# Control_Levitador.net
KiCad netlist of a schematic drawn in Altium Designer
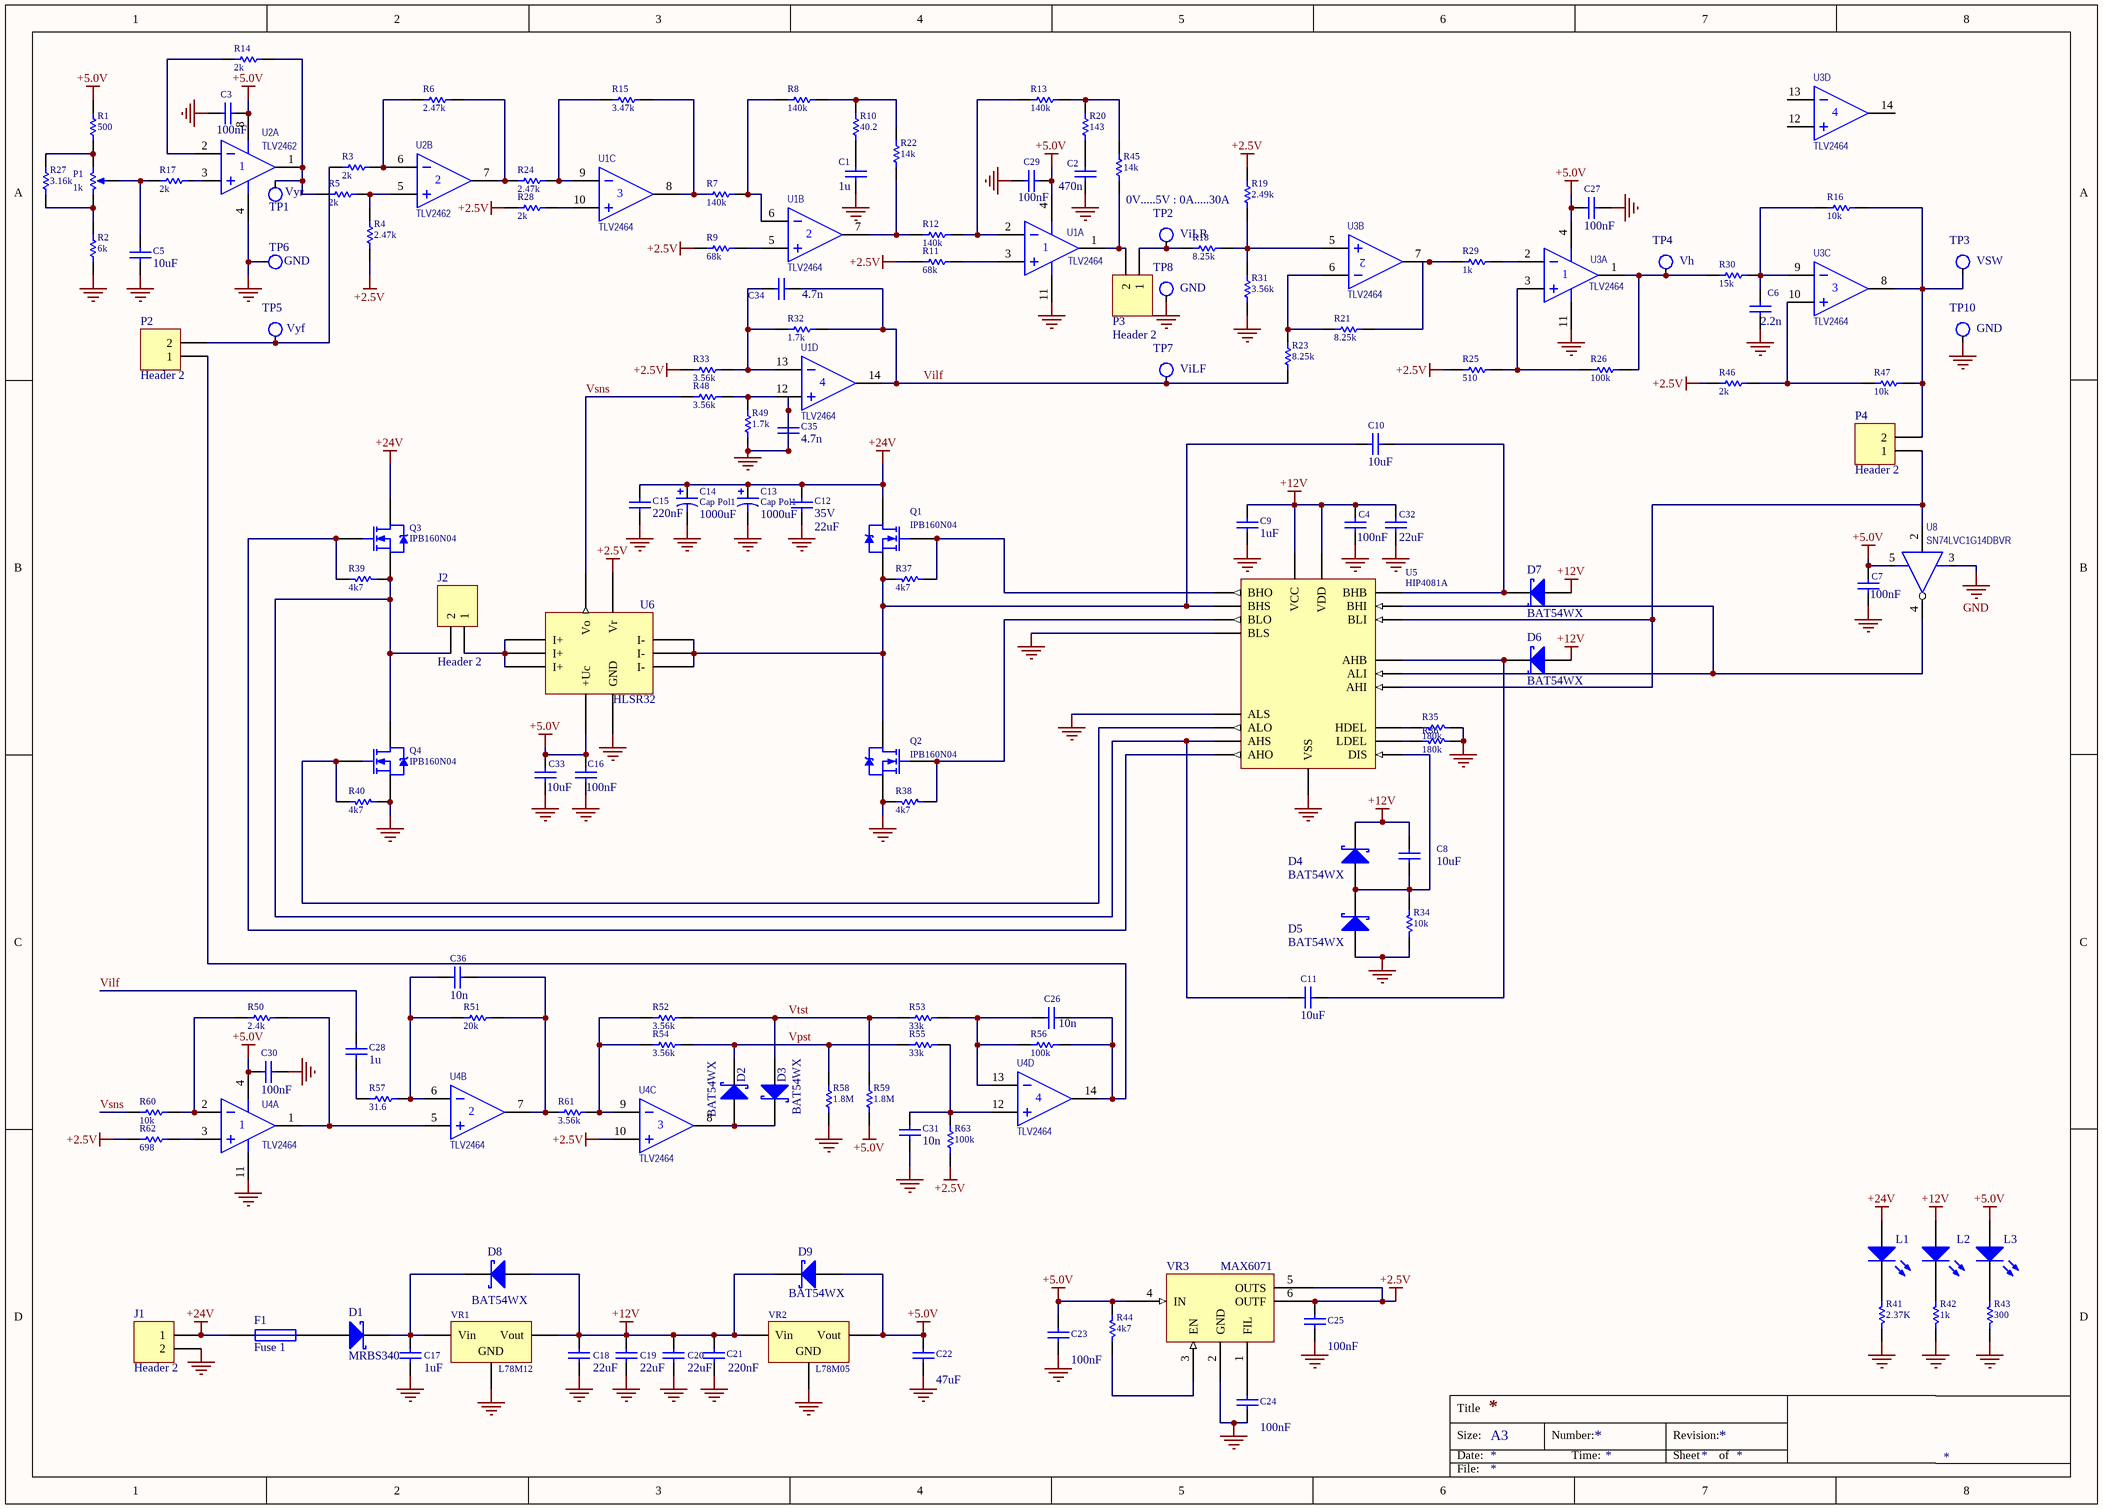
[diagram p0: Control Levitador.SchDoc]

(export (version "E")
  (design (tool "Eeschema 10.0.6"))
  (components
    (comp (ref "C1")
      (value "1u")
      (footprint "C1206")
      (description "Capacitor Chip 1206")
      (fields (field (name "VOLTAGE") "50V") (field (name "PUBLISHER") "Altium Limited"))
      (libsource (lib "Discretos") (part "C1206"))
    )
    (comp (ref "C2")
      (value "470n")
      (footprint "C1206")
      (description "Capacitor Chip 1206")
      (fields (field (name "VOLTAGE") "50V") (field (name "PUBLISHER") "Altium Limited"))
      (libsource (lib "Discretos") (part "C1206"))
    )
    (comp (ref "C3")
      (value "100nF")
      (footprint "C1206")
      (description "Capacitor Chip 1206")
      (fields (field (name "VOLTAGE") "50V") (field (name "PUBLISHER") "Altium Limited"))
      (libsource (lib "Discretos") (part "C1206"))
    )
    (comp (ref "C4")
      (value "100nF")
      (footprint "C1206")
      (description "Capacitor Chip 1206")
      (fields (field (name "VOLTAGE") "50V") (field (name "PUBLISHER") "Altium Limited"))
      (libsource (lib "Discretos") (part "C1206"))
    )
    (comp (ref "C5")
      (value "10uF")
      (footprint "C1206")
      (description "Capacitor Chip 1206")
      (fields (field (name "VOLTAGE") "50V") (field (name "PUBLISHER") "Altium Limited"))
      (libsource (lib "Discretos") (part "C1206"))
    )
    (comp (ref "C6")
      (value "2.2n")
      (footprint "C1206")
      (description "Capacitor Chip 1206")
      (fields (field (name "VOLTAGE") "50V") (field (name "PUBLISHER") "Altium Limited"))
      (libsource (lib "Discretos") (part "C1206"))
    )
    (comp (ref "C7")
      (value "100nF")
      (footprint "C1206")
      (description "Capacitor Chip 1206")
      (fields (field (name "VOLTAGE") "50V") (field (name "PUBLISHER") "Altium Limited"))
      (libsource (lib "Discretos") (part "C1206"))
    )
    (comp (ref "C8")
      (value "10uF")
      (footprint "C1206")
      (description "Capacitor Chip 1206")
      (fields (field (name "VOLTAGE") "50V") (field (name "PUBLISHER") "Altium Limited"))
      (libsource (lib "Discretos") (part "C1206"))
    )
    (comp (ref "C9")
      (value "1uF")
      (footprint "C1206")
      (description "Capacitor Chip 1206")
      (fields (field (name "VOLTAGE") "50V") (field (name "PUBLISHER") "Altium Limited"))
      (libsource (lib "Discretos") (part "C1206"))
    )
    (comp (ref "C10")
      (value "10uF")
      (footprint "C1206")
      (description "Capacitor Chip 1206")
      (fields (field (name "VOLTAGE") "50V") (field (name "PUBLISHER") "Altium Limited"))
      (libsource (lib "Discretos") (part "C1206"))
    )
    (comp (ref "C11")
      (value "10uF")
      (footprint "C1206")
      (description "Capacitor Chip 1206")
      (fields (field (name "VOLTAGE") "50V") (field (name "PUBLISHER") "Altium Limited"))
      (libsource (lib "Discretos") (part "C1206"))
    )
    (comp (ref "C12")
      (value "22uF")
      (footprint "C0805")
      (description "Capacitor Chip 1206")
      (fields (field (name "VOLTAGE") "35V") (field (name "PUBLISHER") "Altium Limited"))
      (libsource (lib "Discretos") (part "C1206"))
    )
    (comp (ref "C13")
      (value "Cap Pol1")
      (footprint "ALU CASE P")
      (description "Polarized Capacitor (Radial)")
      (fields (field (name "ALTIUM_VALUE") "1000uF") (field (name "PUBLISHER") "Altium Limited"))
      (libsource (lib "Miscellaneous Devices") (part "Cap Pol1"))
    )
    (comp (ref "C14")
      (value "Cap Pol1")
      (footprint "ALU CASE P")
      (description "Polarized Capacitor (Radial)")
      (fields (field (name "ALTIUM_VALUE") "1000uF") (field (name "PUBLISHER") "Altium Limited"))
      (libsource (lib "Miscellaneous Devices") (part "Cap Pol1"))
    )
    (comp (ref "C15")
      (value "220nF")
      (footprint "C1206")
      (description "Capacitor Chip 1206")
      (fields (field (name "VOLTAGE") "50V") (field (name "PUBLISHER") "Altium Limited"))
      (libsource (lib "Discretos") (part "C1206"))
    )
    (comp (ref "C16")
      (value "100nF")
      (footprint "C1206")
      (description "Capacitor Chip 1206")
      (fields (field (name "VOLTAGE") "50V") (field (name "PUBLISHER") "Altium Limited"))
      (libsource (lib "Discretos") (part "C1206"))
    )
    (comp (ref "C17")
      (value "1uF")
      (footprint "C1206")
      (description "Capacitor Chip 1206")
      (fields (field (name "VOLTAGE") "35V") (field (name "PUBLISHER") "Altium Limited"))
      (libsource (lib "Discretos") (part "C1206"))
    )
    (comp (ref "C18")
      (value "22uF")
      (footprint "C1206")
      (description "Capacitor Chip 1206")
      (fields (field (name "VOLTAGE") "16V") (field (name "PUBLISHER") "Altium Limited"))
      (libsource (lib "Discretos") (part "C1206"))
    )
    (comp (ref "C19")
      (value "22uF")
      (footprint "C1206")
      (description "Capacitor Chip 1206")
      (fields (field (name "VOLTAGE") "16V") (field (name "PUBLISHER") "Altium Limited"))
      (libsource (lib "Discretos") (part "C1206"))
    )
    (comp (ref "C20")
      (value "22uF")
      (footprint "C1206")
      (description "Capacitor Chip 1206")
      (fields (field (name "VOLTAGE") "16V") (field (name "PUBLISHER") "Altium Limited"))
      (libsource (lib "Discretos") (part "C1206"))
    )
    (comp (ref "C21")
      (value "220nF")
      (footprint "C1206")
      (description "Capacitor Chip 1206")
      (fields (field (name "VOLTAGE") "35V") (field (name "PUBLISHER") "Altium Limited"))
      (libsource (lib "Discretos") (part "C1206"))
    )
    (comp (ref "C22")
      (value "47uF")
      (footprint "C1206")
      (description "Capacitor Chip 1206")
      (fields (field (name "VOLTAGE") "6.3V") (field (name "PUBLISHER") "Altium Limited"))
      (libsource (lib "Discretos") (part "C1206"))
    )
    (comp (ref "C23")
      (value "100nF")
      (footprint "C1206")
      (description "Capacitor Chip 1206")
      (fields (field (name "VOLTAGE") "50V") (field (name "PUBLISHER") "Altium Limited"))
      (libsource (lib "Discretos") (part "C1206"))
    )
    (comp (ref "C24")
      (value "100nF")
      (footprint "C1206")
      (description "Capacitor Chip 1206")
      (fields (field (name "VOLTAGE") "50V") (field (name "PUBLISHER") "Altium Limited"))
      (libsource (lib "Discretos") (part "C1206"))
    )
    (comp (ref "C25")
      (value "100nF")
      (footprint "C1206")
      (description "Capacitor Chip 1206")
      (fields (field (name "VOLTAGE") "50V") (field (name "PUBLISHER") "Altium Limited"))
      (libsource (lib "Discretos") (part "C1206"))
    )
    (comp (ref "C26")
      (value "10n")
      (footprint "C1206")
      (description "Capacitor Chip 1206")
      (fields (field (name "VOLTAGE") "50V") (field (name "PUBLISHER") "Altium Limited"))
      (libsource (lib "Discretos") (part "C1206"))
    )
    (comp (ref "C27")
      (value "100nF")
      (footprint "C1206")
      (description "Capacitor Chip 1206")
      (fields (field (name "VOLTAGE") "50V") (field (name "PUBLISHER") "Altium Limited"))
      (libsource (lib "Discretos") (part "C1206"))
    )
    (comp (ref "C28")
      (value "1u")
      (footprint "C1206")
      (description "Capacitor Chip 1206")
      (fields (field (name "VOLTAGE") "50V") (field (name "PUBLISHER") "Altium Limited"))
      (libsource (lib "Discretos") (part "C1206"))
    )
    (comp (ref "C29")
      (value "100nF")
      (footprint "C1206")
      (description "Capacitor Chip 1206")
      (fields (field (name "VOLTAGE") "50V") (field (name "PUBLISHER") "Altium Limited"))
      (libsource (lib "Discretos") (part "C1206"))
    )
    (comp (ref "C30")
      (value "100nF")
      (footprint "C1206")
      (description "Capacitor Chip 1206")
      (fields (field (name "VOLTAGE") "50V") (field (name "PUBLISHER") "Altium Limited"))
      (libsource (lib "Discretos") (part "C1206"))
    )
    (comp (ref "C31")
      (value "10n")
      (footprint "C1206")
      (description "Capacitor Chip 1206")
      (fields (field (name "VOLTAGE") "50V") (field (name "PUBLISHER") "Altium Limited"))
      (libsource (lib "Discretos") (part "C1206"))
    )
    (comp (ref "C32")
      (value "22uF")
      (footprint "C1206")
      (description "Capacitor Chip 1206")
      (fields (field (name "VOLTAGE") "50V") (field (name "PUBLISHER") "Altium Limited"))
      (libsource (lib "Discretos") (part "C1206"))
    )
    (comp (ref "C33")
      (value "10uF")
      (footprint "C1206")
      (description "Capacitor Chip 1206")
      (fields (field (name "VOLTAGE") "50V") (field (name "PUBLISHER") "Altium Limited"))
      (libsource (lib "Discretos") (part "C1206"))
    )
    (comp (ref "C34")
      (value "4.7n")
      (footprint "C1206")
      (description "Capacitor Chip 1206")
      (fields (field (name "VOLTAGE") "50V") (field (name "PUBLISHER") "Altium Limited"))
      (libsource (lib "Discretos") (part "C1206"))
    )
    (comp (ref "C35")
      (value "4.7n")
      (footprint "C1206")
      (description "Capacitor Chip 1206")
      (fields (field (name "VOLTAGE") "50V") (field (name "PUBLISHER") "Altium Limited"))
      (libsource (lib "Discretos") (part "C1206"))
    )
    (comp (ref "C36")
      (value "10n")
      (footprint "C1206")
      (description "Capacitor Chip 1206")
      (fields (field (name "VOLTAGE") "50V") (field (name "PUBLISHER") "Altium Limited"))
      (libsource (lib "Discretos") (part "C1206"))
    )
    (comp (ref "D1")
      (value "MRBS340")
      (footprint "DO214AB")
      (description "Schottky Rectifier")
      (fields (field (name "PUBLISHER") "Altium Limited"))
      (libsource (lib "Levitador magnetico") (part "Diode 10TQ035"))
    )
    (comp (ref "D2")
      (value "BAT54WX")
      (footprint "SOD523")
      (description "Schottky Rectifier")
      (fields (field (name "PUBLISHER") "Altium Limited"))
      (libsource (lib "Levitador magnetico") (part "Diode 10TQ035"))
    )
    (comp (ref "D3")
      (value "BAT54WX")
      (footprint "SOD523")
      (description "Schottky Rectifier")
      (fields (field (name "PUBLISHER") "Altium Limited"))
      (libsource (lib "Levitador magnetico") (part "Diode 10TQ035"))
    )
    (comp (ref "D4")
      (value "BAT54WX")
      (footprint "SOD523")
      (description "Schottky Rectifier")
      (fields (field (name "PUBLISHER") "Altium Limited"))
      (libsource (lib "Levitador magnetico") (part "Diode 10TQ035"))
    )
    (comp (ref "D5")
      (value "BAT54WX")
      (footprint "SOD523")
      (description "Schottky Rectifier")
      (fields (field (name "PUBLISHER") "Altium Limited"))
      (libsource (lib "Levitador magnetico") (part "Diode 10TQ035"))
    )
    (comp (ref "D6")
      (value "BAT54WX")
      (footprint "SOD523")
      (description "Schottky Rectifier")
      (fields (field (name "PUBLISHER") "Altium Limited"))
      (libsource (lib "Levitador magnetico") (part "Diode 10TQ035"))
    )
    (comp (ref "D7")
      (value "BAT54WX")
      (footprint "SOD523")
      (description "Schottky Rectifier")
      (fields (field (name "PUBLISHER") "Altium Limited"))
      (libsource (lib "Levitador magnetico") (part "Diode 10TQ035"))
    )
    (comp (ref "D8")
      (value "BAT54WX")
      (footprint "SOD523")
      (description "Schottky Rectifier")
      (fields (field (name "PUBLISHER") "Altium Limited"))
      (libsource (lib "Levitador magnetico") (part "Diode 10TQ035"))
    )
    (comp (ref "D9")
      (value "BAT54WX")
      (footprint "SOD523")
      (description "Schottky Rectifier")
      (fields (field (name "PUBLISHER") "Altium Limited"))
      (libsource (lib "Levitador magnetico") (part "Diode 10TQ035"))
    )
    (comp (ref "F1")
      (value "Fuse 1")
      (footprint "R1206")
      (description "Fuse")
      (fields (field (name "PUBLISHER") "Altium Limited"))
      (libsource (lib "Miscellaneous Devices") (part "Fuse 1"))
    )
    (comp (ref "J1")
      (value "Header 2")
      (footprint "SMKDS5-2-9.5")
      (description "Header, 2-Pin")
      (fields (field (name "PUBLISHER") "Altium Limited"))
      (libsource (lib "") (part "Header 2_1"))
    )
    (comp (ref "J2")
      (value "Header 2")
      (footprint "SMKDS5-2-9.5")
      (description "Header, 2-Pin")
      (fields (field (name "PUBLISHER") "Altium Limited"))
      (libsource (lib "") (part "Header 2_2"))
    )
    (comp (ref "L1")
      (value "LED1")
      (footprint "LED 1206 RED")
      (description "Typical RED GaAs LED")
      (fields (field (name "PUBLISHER") "Altium Limited"))
      (libsource (lib "Miscellaneous Devices") (part "LED1"))
    )
    (comp (ref "L2")
      (value "LED1")
      (footprint "LED 1206 RED")
      (description "Typical RED GaAs LED")
      (fields (field (name "PUBLISHER") "Altium Limited"))
      (libsource (lib "Miscellaneous Devices") (part "LED1"))
    )
    (comp (ref "L3")
      (value "LED1")
      (footprint "LED 1206 RED")
      (description "Typical RED GaAs LED")
      (fields (field (name "PUBLISHER") "Altium Limited"))
      (libsource (lib "Miscellaneous Devices") (part "LED1"))
    )
    (comp (ref "P1")
      (value "1k")
      (footprint "BOR3")
      (description "Potentiometer")
      (fields (field (name "Comment") "RPot") (field (name "PUBLISHER") "Altium Limited"))
      (libsource (lib "Levitador magnetico") (part "RPot"))
    )
    (comp (ref "P2")
      (value "Header 2")
      (footprint "HDR1X2")
      (description "Header, 2-Pin")
      (fields (field (name "PUBLISHER") "Altium Limited"))
      (libsource (lib "Miscellaneous Connectors") (part "Header 2"))
    )
    (comp (ref "P3")
      (value "Header 2")
      (footprint "HDR1X2")
      (description "Header, 2-Pin")
      (fields (field (name "PUBLISHER") "Altium Limited"))
      (libsource (lib "") (part "Header 2_1"))
    )
    (comp (ref "P4")
      (value "Header 2")
      (footprint "HDR1X2")
      (description "Header, 2-Pin")
      (fields (field (name "PUBLISHER") "Altium Limited"))
      (libsource (lib "Miscellaneous Connectors") (part "Header 2"))
    )
    (comp (ref "Q1")
      (value "IPB160N04")
      (footprint "TO263-7S")
      (description "HEXFET N-Channel Power MOSFET")
      (fields (field (name "PUBLISHER") "Altium Limited"))
      (libsource (lib "Levitador magnetico") (part "IRF630S"))
    )
    (comp (ref "Q2")
      (value "IPB160N04")
      (footprint "TO263-7S")
      (description "HEXFET N-Channel Power MOSFET")
      (fields (field (name "PUBLISHER") "Altium Limited"))
      (libsource (lib "Levitador magnetico") (part "IRF630S"))
    )
    (comp (ref "Q3")
      (value "IPB160N04")
      (footprint "TO263-7S")
      (description "HEXFET N-Channel Power MOSFET")
      (fields (field (name "PUBLISHER") "Altium Limited"))
      (libsource (lib "Levitador magnetico") (part "IRF630S"))
    )
    (comp (ref "Q4")
      (value "IPB160N04")
      (footprint "TO263-7S")
      (description "HEXFET N-Channel Power MOSFET")
      (fields (field (name "PUBLISHER") "Altium Limited"))
      (libsource (lib "Levitador magnetico") (part "IRF630S"))
    )
    (comp (ref "R1")
      (value "500")
      (footprint "Levitador_GMI:R1206")
      (description "Resistor Chip; 1/8W;")
      (fields (field (name "MANUFACTURER") "Panasonic") (field (name "TOLERANCE") "1%"))
      (libsource (lib "Levitador_GMI") (part "R1206"))
    )
    (comp (ref "R2")
      (value "6k")
      (footprint "Levitador_GMI:R1206")
      (description "Resistor Chip; 1/8W;")
      (fields (field (name "MANUFACTURER") "Panasonic") (field (name "TOLERANCE") "1%"))
      (libsource (lib "Levitador_GMI") (part "R1206"))
    )
    (comp (ref "R3")
      (value "2k")
      (footprint "Levitador_GMI:R1206")
      (description "Resistor Chip; 1/8W;")
      (fields (field (name "MANUFACTURER") "Panasonic") (field (name "TOLERANCE") "1%"))
      (libsource (lib "Levitador_GMI") (part "R1206"))
    )
    (comp (ref "R4")
      (value "2.47k")
      (footprint "Levitador_GMI:R1206")
      (description "Resistor Chip; 1/8W;")
      (fields (field (name "MANUFACTURER") "Panasonic") (field (name "TOLERANCE") "1%"))
      (libsource (lib "Levitador_GMI") (part "R1206"))
    )
    (comp (ref "R5")
      (value "2k")
      (footprint "Levitador_GMI:R1206")
      (description "Resistor Chip; 1/8W;")
      (fields (field (name "MANUFACTURER") "Panasonic") (field (name "TOLERANCE") "1%"))
      (libsource (lib "Levitador_GMI") (part "R1206"))
    )
    (comp (ref "R6")
      (value "2.47k")
      (footprint "Levitador_GMI:R1206")
      (description "Resistor Chip; 1/8W;")
      (fields (field (name "MANUFACTURER") "Panasonic") (field (name "TOLERANCE") "1%"))
      (libsource (lib "Levitador_GMI") (part "R1206"))
    )
    (comp (ref "R7")
      (value "140k")
      (footprint "Levitador_GMI:R1206")
      (description "Resistor Chip; 1/8W;")
      (fields (field (name "MANUFACTURER") "Panasonic") (field (name "TOLERANCE") "1%"))
      (libsource (lib "Levitador_GMI") (part "R1206"))
    )
    (comp (ref "R8")
      (value "140k")
      (footprint "Levitador_GMI:R1206")
      (description "Resistor Chip; 1/8W;")
      (fields (field (name "MANUFACTURER") "Panasonic") (field (name "TOLERANCE") "1%"))
      (libsource (lib "Levitador_GMI") (part "R1206"))
    )
    (comp (ref "R9")
      (value "68k")
      (footprint "Levitador_GMI:R1206")
      (description "Resistor Chip; 1/8W;")
      (fields (field (name "MANUFACTURER") "Panasonic") (field (name "TOLERANCE") "1%"))
      (libsource (lib "Levitador_GMI") (part "R1206"))
    )
    (comp (ref "R10")
      (value "40.2")
      (footprint "Levitador_GMI:R1206")
      (description "Resistor Chip; 1/8W;")
      (fields (field (name "MANUFACTURER") "Panasonic") (field (name "TOLERANCE") "1%"))
      (libsource (lib "Levitador_GMI") (part "R1206"))
    )
    (comp (ref "R11")
      (value "68k")
      (footprint "Levitador_GMI:R1206")
      (description "Resistor Chip; 1/8W;")
      (fields (field (name "MANUFACTURER") "Panasonic") (field (name "TOLERANCE") "1%"))
      (libsource (lib "Levitador_GMI") (part "R1206"))
    )
    (comp (ref "R12")
      (value "140k")
      (footprint "Levitador_GMI:R1206")
      (description "Resistor Chip; 1/8W;")
      (fields (field (name "MANUFACTURER") "Panasonic") (field (name "TOLERANCE") "1%"))
      (libsource (lib "Levitador_GMI") (part "R1206"))
    )
    (comp (ref "R13")
      (value "140k")
      (footprint "Levitador_GMI:R1206")
      (description "Resistor Chip; 1/8W;")
      (fields (field (name "MANUFACTURER") "Panasonic") (field (name "TOLERANCE") "1%"))
      (libsource (lib "Levitador_GMI") (part "R1206"))
    )
    (comp (ref "R14")
      (value "2k")
      (footprint "Levitador_GMI:R1206")
      (description "Resistor Chip; 1/8W;")
      (fields (field (name "MANUFACTURER") "Panasonic") (field (name "TOLERANCE") "1%"))
      (libsource (lib "Levitador_GMI") (part "R1206"))
    )
    (comp (ref "R15")
      (value "3.47k")
      (footprint "Levitador_GMI:R1206")
      (description "Resistor Chip; 1/8W;")
      (fields (field (name "MANUFACTURER") "Panasonic") (field (name "TOLERANCE") "1%"))
      (libsource (lib "Levitador_GMI") (part "R1206"))
    )
    (comp (ref "R16")
      (value "10k")
      (footprint "Levitador_GMI:R1206")
      (description "Resistor Chip; 1/8W;")
      (fields (field (name "MANUFACTURER") "Panasonic") (field (name "TOLERANCE") "1%"))
      (libsource (lib "Levitador_GMI") (part "R1206"))
    )
    (comp (ref "R17")
      (value "2k")
      (footprint "Levitador_GMI:R1206")
      (description "Resistor Chip; 1/8W;")
      (fields (field (name "MANUFACTURER") "Panasonic") (field (name "TOLERANCE") "1%"))
      (libsource (lib "Levitador_GMI") (part "R1206"))
    )
    (comp (ref "R18")
      (value "8.25k")
      (footprint "Levitador_GMI:R1206")
      (description "Resistor Chip; 1/8W;")
      (fields (field (name "MANUFACTURER") "Panasonic") (field (name "TOLERANCE") "1%"))
      (libsource (lib "Levitador_GMI") (part "R1206"))
    )
    (comp (ref "R19")
      (value "2.49k")
      (footprint "Levitador_GMI:R1206")
      (description "Resistor Chip; 1/8W;")
      (fields (field (name "MANUFACTURER") "Panasonic") (field (name "TOLERANCE") "1%"))
      (libsource (lib "Levitador_GMI") (part "R1206"))
    )
    (comp (ref "R20")
      (value "143")
      (footprint "Levitador_GMI:R1206")
      (description "Resistor Chip; 1/8W;")
      (fields (field (name "MANUFACTURER") "Panasonic") (field (name "TOLERANCE") "1%"))
      (libsource (lib "Levitador_GMI") (part "R1206"))
    )
    (comp (ref "R21")
      (value "8.25k")
      (footprint "Levitador_GMI:R1206")
      (description "Resistor Chip; 1/8W;")
      (fields (field (name "MANUFACTURER") "Panasonic") (field (name "TOLERANCE") "1%"))
      (libsource (lib "Levitador_GMI") (part "R1206"))
    )
    (comp (ref "R22")
      (value "14k")
      (footprint "Levitador_GMI:R1206")
      (description "Resistor Chip; 1/8W;")
      (fields (field (name "MANUFACTURER") "Panasonic") (field (name "TOLERANCE") "1%"))
      (libsource (lib "Levitador_GMI") (part "R1206"))
    )
    (comp (ref "R23")
      (value "8.25k")
      (footprint "Levitador_GMI:R1206")
      (description "Resistor Chip; 1/8W;")
      (fields (field (name "MANUFACTURER") "Panasonic") (field (name "TOLERANCE") "1%"))
      (libsource (lib "Levitador_GMI") (part "R1206"))
    )
    (comp (ref "R24")
      (value "2.47k")
      (footprint "Levitador_GMI:R1206")
      (description "Resistor Chip; 1/8W;")
      (fields (field (name "MANUFACTURER") "Panasonic") (field (name "TOLERANCE") "1%"))
      (libsource (lib "Levitador_GMI") (part "R1206"))
    )
    (comp (ref "R25")
      (value "510")
      (footprint "Levitador_GMI:R1206")
      (description "Resistor Chip; 1/8W;")
      (fields (field (name "MANUFACTURER") "Panasonic") (field (name "TOLERANCE") "1%"))
      (libsource (lib "Levitador_GMI") (part "R1206"))
    )
    (comp (ref "R26")
      (value "100k")
      (footprint "Levitador_GMI:R1206")
      (description "Resistor Chip; 1/8W;")
      (fields (field (name "MANUFACTURER") "Panasonic") (field (name "TOLERANCE") "1%"))
      (libsource (lib "Levitador_GMI") (part "R1206"))
    )
    (comp (ref "R27")
      (value "3.16k")
      (footprint "Levitador_GMI:R1206")
      (description "Resistor Chip; 1/8W;")
      (fields (field (name "MANUFACTURER") "Panasonic") (field (name "TOLERANCE") "1%"))
      (libsource (lib "Levitador_GMI") (part "R1206"))
    )
    (comp (ref "R28")
      (value "2k")
      (footprint "Levitador_GMI:R1206")
      (description "Resistor Chip; 1/8W;")
      (fields (field (name "MANUFACTURER") "Panasonic") (field (name "TOLERANCE") "1%"))
      (libsource (lib "Levitador_GMI") (part "R1206"))
    )
    (comp (ref "R29")
      (value "1k")
      (footprint "Levitador_GMI:R1206")
      (description "Resistor Chip; 1/8W;")
      (fields (field (name "MANUFACTURER") "Panasonic") (field (name "TOLERANCE") "1%"))
      (libsource (lib "Levitador_GMI") (part "R1206"))
    )
    (comp (ref "R30")
      (value "15k")
      (footprint "Levitador_GMI:R1206")
      (description "Resistor Chip; 1/8W;")
      (fields (field (name "MANUFACTURER") "Panasonic") (field (name "TOLERANCE") "1%"))
      (libsource (lib "Levitador_GMI") (part "R1206"))
    )
    (comp (ref "R31")
      (value "3.56k")
      (footprint "Levitador_GMI:R1206")
      (description "Resistor Chip; 1/8W;")
      (fields (field (name "MANUFACTURER") "Panasonic") (field (name "TOLERANCE") "1%"))
      (libsource (lib "Levitador_GMI") (part "R1206"))
    )
    (comp (ref "R32")
      (value "1.7k")
      (footprint "Levitador_GMI:R1206")
      (description "Resistor Chip; 1/8W;")
      (fields (field (name "MANUFACTURER") "Panasonic") (field (name "TOLERANCE") "1%"))
      (libsource (lib "Levitador_GMI") (part "R1206"))
    )
    (comp (ref "R33")
      (value "3.56k")
      (footprint "Levitador_GMI:R1206")
      (description "Resistor Chip; 1/8W;")
      (fields (field (name "MANUFACTURER") "Panasonic") (field (name "TOLERANCE") "1%"))
      (libsource (lib "Levitador_GMI") (part "R1206"))
    )
    (comp (ref "R34")
      (value "10k")
      (footprint "Levitador_GMI:R1206")
      (description "Resistor Chip; 1/8W;")
      (fields (field (name "MANUFACTURER") "Panasonic") (field (name "TOLERANCE") "1%"))
      (libsource (lib "Levitador_GMI") (part "R1206"))
    )
    (comp (ref "R35")
      (value "180k")
      (footprint "Levitador_GMI:R1206")
      (description "Resistor Chip; 1/8W;")
      (fields (field (name "MANUFACTURER") "Panasonic") (field (name "TOLERANCE") "1%"))
      (libsource (lib "Levitador_GMI") (part "R1206"))
    )
    (comp (ref "R36")
      (value "180k")
      (footprint "Levitador_GMI:R1206")
      (description "Resistor Chip; 1/8W;")
      (fields (field (name "MANUFACTURER") "Panasonic") (field (name "TOLERANCE") "1%"))
      (libsource (lib "Levitador_GMI") (part "R1206"))
    )
    (comp (ref "R37")
      (value "4k7")
      (footprint "Levitador_GMI:R1206")
      (description "Resistor Chip; 1/8W;")
      (fields (field (name "MANUFACTURER") "Panasonic") (field (name "TOLERANCE") "1%"))
      (libsource (lib "Levitador_GMI") (part "R1206"))
    )
    (comp (ref "R38")
      (value "4k7")
      (footprint "Levitador_GMI:R1206")
      (description "Resistor Chip; 1/8W;")
      (fields (field (name "MANUFACTURER") "Panasonic") (field (name "TOLERANCE") "1%"))
      (libsource (lib "Levitador_GMI") (part "R1206"))
    )
    (comp (ref "R39")
      (value "4k7")
      (footprint "Levitador_GMI:R1206")
      (description "Resistor Chip; 1/8W;")
      (fields (field (name "MANUFACTURER") "Panasonic") (field (name "TOLERANCE") "1%"))
      (libsource (lib "Levitador_GMI") (part "R1206"))
    )
    (comp (ref "R40")
      (value "4k7")
      (footprint "Levitador_GMI:R1206")
      (description "Resistor Chip; 1/8W;")
      (fields (field (name "MANUFACTURER") "Panasonic") (field (name "TOLERANCE") "1%"))
      (libsource (lib "Levitador_GMI") (part "R1206"))
    )
    (comp (ref "R41")
      (value "2.37K")
      (footprint "Levitador_GMI:R1206")
      (description "Resistor Chip; 1/8W;")
      (fields (field (name "MANUFACTURER") "Panasonic") (field (name "TOLERANCE") "1%"))
      (libsource (lib "Levitador_GMI") (part "R1206"))
    )
    (comp (ref "R42")
      (value "1k")
      (footprint "Levitador_GMI:R1206")
      (description "Resistor Chip; 1/8W;")
      (fields (field (name "MANUFACTURER") "Panasonic") (field (name "TOLERANCE") "1%"))
      (libsource (lib "Levitador_GMI") (part "R1206"))
    )
    (comp (ref "R43")
      (value "300")
      (footprint "Levitador_GMI:R1206")
      (description "Resistor Chip; 1/8W;")
      (fields (field (name "MANUFACTURER") "Panasonic") (field (name "TOLERANCE") "1%"))
      (libsource (lib "Levitador_GMI") (part "R1206"))
    )
    (comp (ref "R44")
      (value "4k7")
      (footprint "Levitador_GMI:R1206")
      (description "Resistor Chip; 1/8W;")
      (fields (field (name "MANUFACTURER") "Panasonic") (field (name "TOLERANCE") "1%"))
      (libsource (lib "Levitador_GMI") (part "R1206"))
    )
    (comp (ref "R45")
      (value "14k")
      (footprint "Levitador_GMI:R1206")
      (description "Resistor Chip; 1/8W;")
      (fields (field (name "MANUFACTURER") "Panasonic") (field (name "TOLERANCE") "1%"))
      (libsource (lib "Levitador_GMI") (part "R1206"))
    )
    (comp (ref "R46")
      (value "2k")
      (footprint "Levitador_GMI:R1206")
      (description "Resistor Chip; 1/8W;")
      (fields (field (name "MANUFACTURER") "Panasonic") (field (name "TOLERANCE") "1%"))
      (libsource (lib "Levitador_GMI") (part "R1206"))
    )
    (comp (ref "R47")
      (value "10k")
      (footprint "Levitador_GMI:R1206")
      (description "Resistor Chip; 1/8W;")
      (fields (field (name "MANUFACTURER") "Panasonic") (field (name "TOLERANCE") "1%"))
      (libsource (lib "Levitador_GMI") (part "R1206"))
    )
    (comp (ref "R48")
      (value "3.56k")
      (footprint "Levitador_GMI:R1206")
      (description "Resistor Chip; 1/8W;")
      (fields (field (name "MANUFACTURER") "Panasonic") (field (name "TOLERANCE") "1%"))
      (libsource (lib "Levitador_GMI") (part "R1206"))
    )
    (comp (ref "R49")
      (value "1.7k")
      (footprint "Levitador_GMI:R1206")
      (description "Resistor Chip; 1/8W;")
      (fields (field (name "MANUFACTURER") "Panasonic") (field (name "TOLERANCE") "1%"))
      (libsource (lib "Levitador_GMI") (part "R1206"))
    )
    (comp (ref "R50")
      (value "2.4k")
      (footprint "Levitador_GMI:R1206")
      (description "Resistor Chip; 1/8W;")
      (fields (field (name "MANUFACTURER") "Panasonic") (field (name "TOLERANCE") "1%"))
      (libsource (lib "Levitador_GMI") (part "R1206"))
    )
    (comp (ref "R51")
      (value "20k")
      (footprint "Levitador_GMI:R1206")
      (description "Resistor Chip; 1/8W;")
      (fields (field (name "MANUFACTURER") "Panasonic") (field (name "TOLERANCE") "1%"))
      (libsource (lib "Levitador_GMI") (part "R1206"))
    )
    (comp (ref "R52")
      (value "3.56k")
      (footprint "Levitador_GMI:R1206")
      (description "Resistor Chip; 1/8W;")
      (fields (field (name "MANUFACTURER") "Panasonic") (field (name "TOLERANCE") "1%"))
      (libsource (lib "Levitador_GMI") (part "R1206"))
    )
    (comp (ref "R53")
      (value "33k")
      (footprint "Levitador_GMI:R1206")
      (description "Resistor Chip; 1/8W;")
      (fields (field (name "MANUFACTURER") "Panasonic") (field (name "TOLERANCE") "1%"))
      (libsource (lib "Levitador_GMI") (part "R1206"))
    )
    (comp (ref "R54")
      (value "3.56k")
      (footprint "Levitador_GMI:R1206")
      (description "Resistor Chip; 1/8W;")
      (fields (field (name "MANUFACTURER") "Panasonic") (field (name "TOLERANCE") "1%"))
      (libsource (lib "Levitador_GMI") (part "R1206"))
    )
    (comp (ref "R55")
      (value "33k")
      (footprint "Levitador_GMI:R1206")
      (description "Resistor Chip; 1/8W;")
      (fields (field (name "MANUFACTURER") "Panasonic") (field (name "TOLERANCE") "1%"))
      (libsource (lib "Levitador_GMI") (part "R1206"))
    )
    (comp (ref "R56")
      (value "100k")
      (footprint "Levitador_GMI:R1206")
      (description "Resistor Chip; 1/8W;")
      (fields (field (name "MANUFACTURER") "Panasonic") (field (name "TOLERANCE") "1%"))
      (libsource (lib "Levitador_GMI") (part "R1206"))
    )
    (comp (ref "R57")
      (value "31.6")
      (footprint "Levitador_GMI:R1206")
      (description "Resistor Chip; 1/8W;")
      (fields (field (name "MANUFACTURER") "Panasonic") (field (name "TOLERANCE") "1%"))
      (libsource (lib "Levitador_GMI") (part "R1206"))
    )
    (comp (ref "R58")
      (value "1.8M")
      (footprint "Levitador_GMI:R1206")
      (description "Resistor Chip; 1/8W;")
      (fields (field (name "MANUFACTURER") "Panasonic") (field (name "TOLERANCE") "1%"))
      (libsource (lib "Levitador_GMI") (part "R1206"))
    )
    (comp (ref "R59")
      (value "1.8M")
      (footprint "Levitador_GMI:R1206")
      (description "Resistor Chip; 1/8W;")
      (fields (field (name "MANUFACTURER") "Panasonic") (field (name "TOLERANCE") "1%"))
      (libsource (lib "Levitador_GMI") (part "R1206"))
    )
    (comp (ref "R60")
      (value "10k")
      (footprint "Levitador_GMI:R1206")
      (description "Resistor Chip; 1/8W;")
      (fields (field (name "MANUFACTURER") "Panasonic") (field (name "TOLERANCE") "1%"))
      (libsource (lib "Levitador_GMI") (part "R1206"))
    )
    (comp (ref "R61")
      (value "3.56k")
      (footprint "Levitador_GMI:R1206")
      (description "Resistor Chip; 1/8W;")
      (fields (field (name "MANUFACTURER") "Panasonic") (field (name "TOLERANCE") "1%"))
      (libsource (lib "Levitador_GMI") (part "R1206"))
    )
    (comp (ref "R62")
      (value "698")
      (footprint "Levitador_GMI:R1206")
      (description "Resistor Chip; 1/8W;")
      (fields (field (name "MANUFACTURER") "Panasonic") (field (name "TOLERANCE") "1%"))
      (libsource (lib "Levitador_GMI") (part "R1206"))
    )
    (comp (ref "R63")
      (value "100k")
      (footprint "Levitador_GMI:R1206")
      (description "Resistor Chip; 1/8W;")
      (fields (field (name "MANUFACTURER") "Panasonic") (field (name "TOLERANCE") "1%"))
      (libsource (lib "Levitador_GMI") (part "R1206"))
    )
    (comp (ref "TP1")
      (value "Vyr")
      (footprint "TestPoint Keystone 5000 Silver-Red")
      (description "Test point")
      (libsource (lib "Terminales") (part "Tespoint"))
    )
    (comp (ref "TP2")
      (value "ViLR")
      (footprint "TestPoint Keystone 5000 Silver-Red")
      (description "Test point")
      (libsource (lib "Terminales") (part "Tespoint"))
    )
    (comp (ref "TP3")
      (value "VSW")
      (footprint "TestPoint Keystone 5000 Silver-Red")
      (description "Test point")
      (libsource (lib "Terminales") (part "Tespoint"))
    )
    (comp (ref "TP4")
      (value "Vh")
      (footprint "TestPoint Keystone 5000 Silver-Red")
      (description "Test point")
      (libsource (lib "Terminales") (part "Tespoint"))
    )
    (comp (ref "TP5")
      (value "Vyf")
      (footprint "TestPoint Keystone 5000 Silver-Red")
      (description "Test point")
      (libsource (lib "Terminales") (part "Tespoint"))
    )
    (comp (ref "TP6")
      (value "GND")
      (footprint "TestPoint Keystone 5000 Silver-Red")
      (description "Test point")
      (libsource (lib "Terminales") (part "Tespoint"))
    )
    (comp (ref "TP7")
      (value "ViLF")
      (footprint "TestPoint Keystone 5000 Silver-Red")
      (description "Test point")
      (libsource (lib "Terminales") (part "Tespoint"))
    )
    (comp (ref "TP8")
      (value "GND")
      (footprint "TestPoint Keystone 5000 Silver-Red")
      (description "Test point")
      (libsource (lib "Terminales") (part "Tespoint"))
    )
    (comp (ref "TP10")
      (value "GND")
      (footprint "TestPoint Keystone 5000 Silver-Red")
      (description "Test point")
      (libsource (lib "Terminales") (part "Tespoint"))
    )
    (comp (ref "U1")
      (value "TLV2464")
      (footprint "SOIC14")
      (description "Dual Low-Power Operational Amplifier")
      (fields (field (name "PUBLISHER") "Altium Limited"))
      (libsource (lib "Levitador") (part "TLV2464"))
    )
    (comp (ref "U2")
      (value "TLV2462")
      (footprint "SOIC8")
      (description "Dual Low-Power Operational Amplifier")
      (fields (field (name "PUBLISHER") "Altium Limited"))
      (libsource (lib "CTRL_Levitador") (part "TLV2462"))
    )
    (comp (ref "U3")
      (value "TLV2464")
      (footprint "SOIC14")
      (description "Dual Low-Power Operational Amplifier")
      (fields (field (name "PUBLISHER") "Altium Limited"))
      (libsource (lib "Levitador") (part "TLV2464"))
    )
    (comp (ref "U4")
      (value "TLV2464")
      (footprint "SOIC14")
      (description "Dual Low-Power Operational Amplifier")
      (fields (field (name "PUBLISHER") "Altium Limited"))
      (libsource (lib "Levitador") (part "TLV2464"))
    )
    (comp (ref "U5")
      (value "HIP4081A")
      (footprint "SOIC20")
      (description "INTERSIL, 80V, 2.5A peak, High Frequency Full Bridge FET Driver")
      (fields (field (name "MANUFACTURER_PART_NUMBER") "HIP4081AIBZ"))
      (libsource (lib "Levitador_GMI") (part "HIP4081A"))
    )
    (comp (ref "U6")
      (value "HLSR32")
      (footprint "HSLR-P")
      (description "Hall Effect Current Sensor")
      (libsource (lib "Sensores") (part "HSLR32"))
    )
    (comp (ref "U8")
      (value "SN74LVC1G14DBVR")
      (footprint "SOT23-5")
      (description "Schmitt-Trigger Inverter")
      (fields (field (name "PUBLISHER") "Altium Limited"))
      (libsource (lib "Levitador") (part "SN74LVC1G14DBVR"))
    )
    (comp (ref "VR1")
      (value "L78M12")
      (footprint "TO252-AA")
      (description "Voltage Regulator")
      (fields (field (name "PUBLISHER") "Altium Limited"))
      (libsource (lib "Levitador magnetico") (part "Volt Reg"))
    )
    (comp (ref "VR2")
      (value "L78M05")
      (footprint "TO252-AA")
      (description "Voltage Regulator")
      (fields (field (name "PUBLISHER") "Altium Limited"))
      (libsource (lib "Levitador magnetico") (part "Volt Reg"))
    )
    (comp (ref "VR3")
      (value "MAX6071")
      (footprint "SOT23-6")
      (libsource (lib "Fuentes Alimentacion") (part "MAX6070"))
    )
  )
  (nets
    (net (code "1") (name "+2.5V") (class "Default")
      (node (ref "C25") (pin "2") (pinfunction "2_2") (pintype "passive"))
      (node (ref "R11") (pin "2") (pinfunction "2_2") (pintype "passive"))
      (node (ref "R19") (pin "2") (pinfunction "2_2") (pintype "passive"))
      (node (ref "R25") (pin "2") (pinfunction "2_2") (pintype "passive"))
      (node (ref "R28") (pin "1") (pinfunction "1_1") (pintype "passive"))
      (node (ref "R33") (pin "1") (pinfunction "1_1") (pintype "passive"))
      (node (ref "R4") (pin "1") (pinfunction "1_1") (pintype "passive"))
      (node (ref "R46") (pin "2") (pinfunction "2_2") (pintype "passive"))
      (node (ref "R62") (pin "1") (pinfunction "1_1") (pintype "passive"))
      (node (ref "R63") (pin "2") (pinfunction "2_2") (pintype "passive"))
      (node (ref "R9") (pin "1") (pinfunction "1_1") (pintype "passive"))
      (node (ref "U4") (pin "10") (pinfunction "IN+_10") (pintype "passive"))
      (node (ref "U6") (pin "1") (pinfunction "Vr_1") (pintype "passive"))
      (node (ref "VR3") (pin "5") (pinfunction "OUTS_5") (pintype "passive"))
      (node (ref "VR3") (pin "6") (pinfunction "OUTF_6") (pintype "passive"))
    )
    (net (code "2") (name "+5.0V") (class "Default")
      (node (ref "C16") (pin "2") (pinfunction "2_2") (pintype "passive"))
      (node (ref "C22") (pin "2") (pinfunction "2_2") (pintype "passive"))
      (node (ref "C23") (pin "2") (pinfunction "2_2") (pintype "passive"))
      (node (ref "C27") (pin "2") (pinfunction "2_2") (pintype "passive"))
      (node (ref "C29") (pin "2") (pinfunction "2_2") (pintype "passive"))
      (node (ref "C3") (pin "2") (pinfunction "2_2") (pintype "passive"))
      (node (ref "C30") (pin "2") (pinfunction "2_2") (pintype "passive"))
      (node (ref "C33") (pin "2") (pinfunction "2_2") (pintype "passive"))
      (node (ref "C7") (pin "2") (pinfunction "2_2") (pintype "passive"))
      (node (ref "D9") (pin "1") (pinfunction "A_1") (pintype "passive"))
      (node (ref "L3") (pin "1") (pinfunction "A_1") (pintype "passive"))
      (node (ref "R1") (pin "2") (pinfunction "2_2") (pintype "passive"))
      (node (ref "R44") (pin "2") (pinfunction "2_2") (pintype "passive"))
      (node (ref "R59") (pin "1") (pinfunction "1_1") (pintype "passive"))
      (node (ref "U1") (pin "4") (pinfunction "V+_4") (pintype "power_in"))
      (node (ref "U2") (pin "8") (pinfunction "V+_8") (pintype "power_in"))
      (node (ref "U3") (pin "4") (pinfunction "V+_4") (pintype "power_in"))
      (node (ref "U4") (pin "4") (pinfunction "V+_4") (pintype "power_in"))
      (node (ref "U6") (pin "4") (pinfunction "+Uc_4") (pintype "power_in"))
      (node (ref "U8") (pin "5") (pinfunction "V+_5") (pintype "power_in"))
      (node (ref "VR2") (pin "3") (pinfunction "Vout_3") (pintype "passive"))
      (node (ref "VR3") (pin "4") (pinfunction "IN_4") (pintype "input"))
    )
    (net (code "3") (name "+12V") (class "Default")
      (node (ref "C18") (pin "2") (pinfunction "2_2") (pintype "passive"))
      (node (ref "C19") (pin "2") (pinfunction "2_2") (pintype "passive"))
      (node (ref "C20") (pin "2") (pinfunction "2_2") (pintype "passive"))
      (node (ref "C21") (pin "2") (pinfunction "2_2") (pintype "passive"))
      (node (ref "C32") (pin "2") (pinfunction "2_2") (pintype "passive"))
      (node (ref "C4") (pin "2") (pinfunction "2_2") (pintype "passive"))
      (node (ref "C8") (pin "1") (pinfunction "1_1") (pintype "passive"))
      (node (ref "C9") (pin "2") (pinfunction "2_2") (pintype "passive"))
      (node (ref "D4") (pin "2") (pinfunction "K_2") (pintype "passive"))
      (node (ref "D6") (pin "1") (pinfunction "A_1") (pintype "passive"))
      (node (ref "D7") (pin "1") (pinfunction "A_1") (pintype "passive"))
      (node (ref "D8") (pin "1") (pinfunction "A_1") (pintype "passive"))
      (node (ref "D9") (pin "2") (pinfunction "K_2") (pintype "passive"))
      (node (ref "L2") (pin "1") (pinfunction "A_1") (pintype "passive"))
      (node (ref "U5") (pin "15") (pinfunction "VCC_15") (pintype "power_in"))
      (node (ref "U5") (pin "16") (pinfunction "VDD_16") (pintype "power_in"))
      (node (ref "VR1") (pin "3") (pinfunction "Vout_3") (pintype "passive"))
      (node (ref "VR2") (pin "1") (pinfunction "Vin_1") (pintype "passive"))
    )
    (net (code "4") (name "+24V") (class "Default")
      (node (ref "C12") (pin "2") (pinfunction "2_2") (pintype "passive"))
      (node (ref "C13") (pin "1") (pinfunction "1_1") (pintype "passive"))
      (node (ref "C14") (pin "1") (pinfunction "1_1") (pintype "passive"))
      (node (ref "C15") (pin "2") (pinfunction "2_2") (pintype "passive"))
      (node (ref "F1") (pin "1") (pinfunction "1_1") (pintype "passive"))
      (node (ref "J1") (pin "1") (pinfunction "1_1") (pintype "passive"))
      (node (ref "L1") (pin "1") (pinfunction "A_1") (pintype "passive"))
      (node (ref "Q1") (pin "4") (pinfunction "D_4") (pintype "passive"))
      (node (ref "Q3") (pin "4") (pinfunction "D_4") (pintype "passive"))
    )
    (net (code "5") (name "/Vilf") (class "Default")
      (node (ref "C28") (pin "1") (pinfunction "1_1") (pintype "passive"))
      (node (ref "C34") (pin "2") (pinfunction "2_2") (pintype "passive"))
      (node (ref "R23") (pin "1") (pinfunction "1_1") (pintype "passive"))
      (node (ref "R32") (pin "2") (pinfunction "2_2") (pintype "passive"))
      (node (ref "TP7") (pin "1") (pinfunction "1_1") (pintype "passive"))
      (node (ref "U1") (pin "14") (pinfunction "OUT_14") (pintype "passive"))
    )
    (net (code "6") (name "/Vpst") (class "Default")
      (node (ref "D2") (pin "2") (pinfunction "K_2") (pintype "passive"))
      (node (ref "R54") (pin "2") (pinfunction "2_2") (pintype "passive"))
      (node (ref "R55") (pin "2") (pinfunction "2_2") (pintype "passive"))
      (node (ref "R58") (pin "2") (pinfunction "2_2") (pintype "passive"))
    )
    (net (code "7") (name "/Vsns") (class "Default")
      (node (ref "R48") (pin "2") (pinfunction "2_2") (pintype "passive"))
      (node (ref "R60") (pin "1") (pinfunction "1_1") (pintype "passive"))
      (node (ref "U6") (pin "2") (pinfunction "Vo_2") (pintype "output"))
    )
    (net (code "8") (name "/Vtst") (class "Default")
      (node (ref "D3") (pin "1") (pinfunction "A_1") (pintype "passive"))
      (node (ref "R52") (pin "2") (pinfunction "2_2") (pintype "passive"))
      (node (ref "R53") (pin "2") (pinfunction "2_2") (pintype "passive"))
      (node (ref "R59") (pin "2") (pinfunction "2_2") (pintype "passive"))
    )
    (net (code "9") (name "GND") (class "Default")
      (node (ref "C1") (pin "1") (pinfunction "1_1") (pintype "passive"))
      (node (ref "C12") (pin "1") (pinfunction "1_1") (pintype "passive"))
      (node (ref "C13") (pin "2") (pinfunction "2_2") (pintype "passive"))
      (node (ref "C14") (pin "2") (pinfunction "2_2") (pintype "passive"))
      (node (ref "C15") (pin "1") (pinfunction "1_1") (pintype "passive"))
      (node (ref "C16") (pin "1") (pinfunction "1_1") (pintype "passive"))
      (node (ref "C17") (pin "1") (pinfunction "1_1") (pintype "passive"))
      (node (ref "C18") (pin "1") (pinfunction "1_1") (pintype "passive"))
      (node (ref "C19") (pin "1") (pinfunction "1_1") (pintype "passive"))
      (node (ref "C2") (pin "1") (pinfunction "1_1") (pintype "passive"))
      (node (ref "C20") (pin "1") (pinfunction "1_1") (pintype "passive"))
      (node (ref "C21") (pin "1") (pinfunction "1_1") (pintype "passive"))
      (node (ref "C22") (pin "1") (pinfunction "1_1") (pintype "passive"))
      (node (ref "C23") (pin "1") (pinfunction "1_1") (pintype "passive"))
      (node (ref "C24") (pin "1") (pinfunction "1_1") (pintype "passive"))
      (node (ref "C25") (pin "1") (pinfunction "1_1") (pintype "passive"))
      (node (ref "C27") (pin "1") (pinfunction "1_1") (pintype "passive"))
      (node (ref "C29") (pin "1") (pinfunction "1_1") (pintype "passive"))
      (node (ref "C3") (pin "1") (pinfunction "1_1") (pintype "passive"))
      (node (ref "C30") (pin "1") (pinfunction "1_1") (pintype "passive"))
      (node (ref "C31") (pin "1") (pinfunction "1_1") (pintype "passive"))
      (node (ref "C32") (pin "1") (pinfunction "1_1") (pintype "passive"))
      (node (ref "C33") (pin "1") (pinfunction "1_1") (pintype "passive"))
      (node (ref "C35") (pin "1") (pinfunction "1_1") (pintype "passive"))
      (node (ref "C35") (pin "2") (pinfunction "2_2") (pintype "passive"))
      (node (ref "C4") (pin "1") (pinfunction "1_1") (pintype "passive"))
      (node (ref "C5") (pin "1") (pinfunction "1_1") (pintype "passive"))
      (node (ref "C6") (pin "1") (pinfunction "1_1") (pintype "passive"))
      (node (ref "C7") (pin "1") (pinfunction "1_1") (pintype "passive"))
      (node (ref "C9") (pin "1") (pinfunction "1_1") (pintype "passive"))
      (node (ref "D5") (pin "1") (pinfunction "A_1") (pintype "passive"))
      (node (ref "J1") (pin "2") (pinfunction "2_2") (pintype "passive"))
      (node (ref "Q2") (pin "2") (pinfunction "S_2") (pintype "passive"))
      (node (ref "Q2") (pin "3") (pinfunction "S_3") (pintype "passive"))
      (node (ref "Q2") (pin "5") (pinfunction "S_5") (pintype "passive"))
      (node (ref "Q2") (pin "6") (pinfunction "S_6") (pintype "passive"))
      (node (ref "Q2") (pin "7") (pinfunction "S_7") (pintype "passive"))
      (node (ref "Q4") (pin "2") (pinfunction "S_2") (pintype "passive"))
      (node (ref "Q4") (pin "3") (pinfunction "S_3") (pintype "passive"))
      (node (ref "Q4") (pin "5") (pinfunction "S_5") (pintype "passive"))
      (node (ref "Q4") (pin "6") (pinfunction "S_6") (pintype "passive"))
      (node (ref "Q4") (pin "7") (pinfunction "S_7") (pintype "passive"))
      (node (ref "R2") (pin "1") (pinfunction "1_1") (pintype "passive"))
      (node (ref "R31") (pin "1") (pinfunction "1_1") (pintype "passive"))
      (node (ref "R34") (pin "2") (pinfunction "2_2") (pintype "passive"))
      (node (ref "R35") (pin "1") (pinfunction "1_1") (pintype "passive"))
      (node (ref "R36") (pin "1") (pinfunction "1_1") (pintype "passive"))
      (node (ref "R38") (pin "2") (pinfunction "2_2") (pintype "passive"))
      (node (ref "R40") (pin "1") (pinfunction "1_1") (pintype "passive"))
      (node (ref "R41") (pin "1") (pinfunction "1_1") (pintype "passive"))
      (node (ref "R42") (pin "2") (pinfunction "2_2") (pintype "passive"))
      (node (ref "R43") (pin "1") (pinfunction "1_1") (pintype "passive"))
      (node (ref "R49") (pin "1") (pinfunction "1_1") (pintype "passive"))
      (node (ref "R58") (pin "1") (pinfunction "1_1") (pintype "passive"))
      (node (ref "TP10") (pin "1") (pinfunction "1_1") (pintype "passive"))
      (node (ref "TP6") (pin "1") (pinfunction "1_1") (pintype "passive"))
      (node (ref "TP8") (pin "1") (pinfunction "1_1") (pintype "passive"))
      (node (ref "U1") (pin "11") (pinfunction "V-_11") (pintype "power_in"))
      (node (ref "U2") (pin "4") (pinfunction "V-_4") (pintype "power_in"))
      (node (ref "U3") (pin "11") (pinfunction "V-_11") (pintype "power_in"))
      (node (ref "U4") (pin "11") (pinfunction "V-_11") (pintype "power_in"))
      (node (ref "U5") (pin "14") (pinfunction "ALS_14") (pintype "passive"))
      (node (ref "U5") (pin "17") (pinfunction "BLS_17") (pintype "passive"))
      (node (ref "U5") (pin "4") (pinfunction "VSS_4") (pintype "power_in"))
      (node (ref "U6") (pin "3") (pinfunction "GND_3") (pintype "power_in"))
      (node (ref "U8") (pin "3") (pinfunction "V-_3") (pintype "power_in"))
      (node (ref "VR1") (pin "4") (pinfunction "GND_4") (pintype "passive"))
      (node (ref "VR2") (pin "4") (pinfunction "GND_4") (pintype "passive"))
      (node (ref "VR3") (pin "2") (pinfunction "GND_2") (pintype "power_in"))
    )
    (net (code "10") (name "Net-(C1-Pad2)") (class "Default")
      (node (ref "C1") (pin "2") (pinfunction "2_2") (pintype "passive"))
      (node (ref "R10") (pin "1") (pinfunction "1_1") (pintype "passive"))
    )
    (net (code "11") (name "Net-(C2-Pad2)") (class "Default")
      (node (ref "C2") (pin "2") (pinfunction "2_2") (pintype "passive"))
      (node (ref "R20") (pin "1") (pinfunction "1_1") (pintype "passive"))
    )
    (net (code "12") (name "Net-(C28-Pad2)") (class "Default")
      (node (ref "C28") (pin "2") (pinfunction "2_2") (pintype "passive"))
      (node (ref "R57") (pin "1") (pinfunction "1_1") (pintype "passive"))
    )
    (net (code "13") (name "Net-(D1-A)") (class "Default")
      (node (ref "D1") (pin "1") (pinfunction "A_1") (pintype "passive"))
      (node (ref "F1") (pin "2") (pinfunction "2_2") (pintype "passive"))
    )
    (net (code "14") (name "Net-(D1-K)") (class "Default")
      (node (ref "C17") (pin "2") (pinfunction "2_2") (pintype "passive"))
      (node (ref "D1") (pin "2") (pinfunction "K_2") (pintype "passive"))
      (node (ref "D8") (pin "2") (pinfunction "K_2") (pintype "passive"))
      (node (ref "VR1") (pin "1") (pinfunction "Vin_1") (pintype "passive"))
    )
    (net (code "15") (name "Net-(D2-A)") (class "Default")
      (node (ref "D2") (pin "1") (pinfunction "A_1") (pintype "passive"))
      (node (ref "D3") (pin "2") (pinfunction "K_2") (pintype "passive"))
      (node (ref "U4") (pin "8") (pinfunction "OUT_8") (pintype "passive"))
    )
    (net (code "16") (name "Net-(D4-A)") (class "Default")
      (node (ref "C8") (pin "2") (pinfunction "2_2") (pintype "passive"))
      (node (ref "D4") (pin "1") (pinfunction "A_1") (pintype "passive"))
      (node (ref "D5") (pin "2") (pinfunction "K_2") (pintype "passive"))
      (node (ref "R34") (pin "1") (pinfunction "1_1") (pintype "passive"))
      (node (ref "U5") (pin "3") (pinfunction "DIS_3") (pintype "input"))
    )
    (net (code "17") (name "Net-(D6-K)") (class "Default")
      (node (ref "C11") (pin "1") (pinfunction "1_1") (pintype "passive"))
      (node (ref "D6") (pin "2") (pinfunction "K_2") (pintype "passive"))
      (node (ref "U5") (pin "10") (pinfunction "AHB_10") (pintype "power_in"))
    )
    (net (code "18") (name "Net-(D7-K)") (class "Default")
      (node (ref "C10") (pin "1") (pinfunction "1_1") (pintype "passive"))
      (node (ref "D7") (pin "2") (pinfunction "K_2") (pintype "passive"))
      (node (ref "U5") (pin "1") (pinfunction "BHB_1") (pintype "power_in"))
    )
    (net (code "19") (name "Net-(J2-Pad1)") (class "Default")
      (node (ref "J2") (pin "1") (pinfunction "1_1") (pintype "passive"))
      (node (ref "U6") (pin "10") (pinfunction "I+_10") (pintype "passive"))
      (node (ref "U6") (pin "8") (pinfunction "I+_8") (pintype "passive"))
      (node (ref "U6") (pin "9") (pinfunction "I+_9") (pintype "passive"))
    )
    (net (code "20") (name "Net-(L1-K)") (class "Default")
      (node (ref "L1") (pin "2") (pinfunction "K_2") (pintype "passive"))
      (node (ref "R41") (pin "2") (pinfunction "2_2") (pintype "passive"))
    )
    (net (code "21") (name "Net-(L2-K)") (class "Default")
      (node (ref "L2") (pin "2") (pinfunction "K_2") (pintype "passive"))
      (node (ref "R42") (pin "1") (pinfunction "1_1") (pintype "passive"))
    )
    (net (code "22") (name "Net-(L3-K)") (class "Default")
      (node (ref "L3") (pin "2") (pinfunction "K_2") (pintype "passive"))
      (node (ref "R43") (pin "2") (pinfunction "2_2") (pintype "passive"))
    )
    (net (code "23") (name "Net-(P1-BOT)") (class "Default")
      (node (ref "P1") (pin "3") (pinfunction "BOT_3") (pintype "passive"))
      (node (ref "R2") (pin "2") (pinfunction "2_2") (pintype "passive"))
      (node (ref "R27") (pin "1") (pinfunction "1_1") (pintype "passive"))
    )
    (net (code "24") (name "Net-(P1-TAP)") (class "Default")
      (node (ref "C5") (pin "2") (pinfunction "2_2") (pintype "passive"))
      (node (ref "P1") (pin "2") (pinfunction "TAP_2") (pintype "passive"))
      (node (ref "R17") (pin "2") (pinfunction "2_2") (pintype "passive"))
    )
    (net (code "25") (name "Net-(P1-TOP)") (class "Default")
      (node (ref "P1") (pin "1") (pinfunction "TOP_1") (pintype "passive"))
      (node (ref "R1") (pin "1") (pinfunction "1_1") (pintype "passive"))
      (node (ref "R27") (pin "2") (pinfunction "2_2") (pintype "passive"))
    )
    (net (code "26") (name "Net-(P2-Pad2)") (class "Default")
      (node (ref "P2") (pin "2") (pinfunction "2_2") (pintype "passive"))
      (node (ref "R3") (pin "2") (pinfunction "2_2") (pintype "passive"))
      (node (ref "TP5") (pin "1") (pinfunction "1_1") (pintype "passive"))
    )
    (net (code "27") (name "Net-(P3-Pad1)") (class "Default")
      (node (ref "P3") (pin "1") (pinfunction "1_1") (pintype "passive"))
      (node (ref "R18") (pin "2") (pinfunction "2_2") (pintype "passive"))
      (node (ref "TP2") (pin "1") (pinfunction "1_1") (pintype "passive"))
    )
    (net (code "28") (name "Net-(Q1-G)") (class "Default")
      (node (ref "Q1") (pin "1") (pinfunction "G_1") (pintype "passive"))
      (node (ref "R37") (pin "1") (pinfunction "1_1") (pintype "passive"))
      (node (ref "U5") (pin "20") (pinfunction "BHO_20") (pintype "output"))
    )
    (net (code "29") (name "Net-(Q2-D)") (class "Default")
      (node (ref "C10") (pin "2") (pinfunction "2_2") (pintype "passive"))
      (node (ref "Q1") (pin "2") (pinfunction "S_2") (pintype "passive"))
      (node (ref "Q1") (pin "3") (pinfunction "S_3") (pintype "passive"))
      (node (ref "Q1") (pin "5") (pinfunction "S_5") (pintype "passive"))
      (node (ref "Q1") (pin "6") (pinfunction "S_6") (pintype "passive"))
      (node (ref "Q1") (pin "7") (pinfunction "S_7") (pintype "passive"))
      (node (ref "Q2") (pin "4") (pinfunction "D_4") (pintype "passive"))
      (node (ref "R37") (pin "2") (pinfunction "2_2") (pintype "passive"))
      (node (ref "U5") (pin "19") (pinfunction "BHS_19") (pintype "passive"))
      (node (ref "U6") (pin "5") (pinfunction "I-_5") (pintype "passive"))
      (node (ref "U6") (pin "6") (pinfunction "I-_6") (pintype "passive"))
      (node (ref "U6") (pin "7") (pinfunction "I-_7") (pintype "passive"))
    )
    (net (code "30") (name "Net-(Q2-G)") (class "Default")
      (node (ref "Q2") (pin "1") (pinfunction "G_1") (pintype "passive"))
      (node (ref "R38") (pin "1") (pinfunction "1_1") (pintype "passive"))
      (node (ref "U5") (pin "18") (pinfunction "BLO_18") (pintype "output"))
    )
    (net (code "31") (name "Net-(Q3-G)") (class "Default")
      (node (ref "Q3") (pin "1") (pinfunction "G_1") (pintype "passive"))
      (node (ref "R39") (pin "2") (pinfunction "2_2") (pintype "passive"))
      (node (ref "U5") (pin "11") (pinfunction "AHO_11") (pintype "output"))
    )
    (net (code "32") (name "Net-(Q4-D)") (class "Default")
      (node (ref "C11") (pin "2") (pinfunction "2_2") (pintype "passive"))
      (node (ref "J2") (pin "2") (pinfunction "2_2") (pintype "passive"))
      (node (ref "Q3") (pin "2") (pinfunction "S_2") (pintype "passive"))
      (node (ref "Q3") (pin "3") (pinfunction "S_3") (pintype "passive"))
      (node (ref "Q3") (pin "5") (pinfunction "S_5") (pintype "passive"))
      (node (ref "Q3") (pin "6") (pinfunction "S_6") (pintype "passive"))
      (node (ref "Q3") (pin "7") (pinfunction "S_7") (pintype "passive"))
      (node (ref "Q4") (pin "4") (pinfunction "D_4") (pintype "passive"))
      (node (ref "R39") (pin "1") (pinfunction "1_1") (pintype "passive"))
      (node (ref "U5") (pin "12") (pinfunction "AHS_12") (pintype "passive"))
    )
    (net (code "33") (name "Net-(Q4-G)") (class "Default")
      (node (ref "Q4") (pin "1") (pinfunction "G_1") (pintype "passive"))
      (node (ref "R40") (pin "2") (pinfunction "2_2") (pintype "passive"))
      (node (ref "U5") (pin "13") (pinfunction "ALO_13") (pintype "output"))
    )
    (net (code "34") (name "Net-(R10-Pad2)") (class "Default")
      (node (ref "R10") (pin "2") (pinfunction "2_2") (pintype "passive"))
      (node (ref "R22") (pin "1") (pinfunction "1_1") (pintype "passive"))
      (node (ref "R8") (pin "2") (pinfunction "2_2") (pintype "passive"))
    )
    (net (code "35") (name "Net-(R13-Pad2)") (class "Default")
      (node (ref "R13") (pin "2") (pinfunction "2_2") (pintype "passive"))
      (node (ref "R20") (pin "2") (pinfunction "2_2") (pintype "passive"))
      (node (ref "R45") (pin "1") (pinfunction "1_1") (pintype "passive"))
    )
    (net (code "36") (name "Net-(U1A-IN+)") (class "Default")
      (node (ref "R11") (pin "1") (pinfunction "1_1") (pintype "passive"))
      (node (ref "U1") (pin "3") (pinfunction "IN+_3") (pintype "passive"))
    )
    (net (code "37") (name "Net-(U1A-IN-)") (class "Default")
      (node (ref "R12") (pin "2") (pinfunction "2_2") (pintype "passive"))
      (node (ref "R13") (pin "1") (pinfunction "1_1") (pintype "passive"))
      (node (ref "U1") (pin "2") (pinfunction "IN-_2") (pintype "passive"))
    )
    (net (code "38") (name "Net-(U1A-OUT)") (class "Default")
      (node (ref "P3") (pin "2") (pinfunction "2_2") (pintype "passive"))
      (node (ref "R45") (pin "2") (pinfunction "2_2") (pintype "passive"))
      (node (ref "U1") (pin "1") (pinfunction "OUT_1") (pintype "passive"))
    )
    (net (code "39") (name "Net-(U1B-IN+)") (class "Default")
      (node (ref "R9") (pin "2") (pinfunction "2_2") (pintype "passive"))
      (node (ref "U1") (pin "5") (pinfunction "IN+_5") (pintype "passive"))
    )
    (net (code "40") (name "Net-(U1B-IN-)") (class "Default")
      (node (ref "R7") (pin "2") (pinfunction "2_2") (pintype "passive"))
      (node (ref "R8") (pin "1") (pinfunction "1_1") (pintype "passive"))
      (node (ref "U1") (pin "6") (pinfunction "IN-_6") (pintype "passive"))
    )
    (net (code "41") (name "Net-(U1B-OUT)") (class "Default")
      (node (ref "R12") (pin "1") (pinfunction "1_1") (pintype "passive"))
      (node (ref "R22") (pin "2") (pinfunction "2_2") (pintype "passive"))
      (node (ref "U1") (pin "7") (pinfunction "OUT_7") (pintype "passive"))
    )
    (net (code "42") (name "Net-(U1C-IN+)") (class "Default")
      (node (ref "R28") (pin "2") (pinfunction "2_2") (pintype "passive"))
      (node (ref "U1") (pin "10") (pinfunction "IN+_10") (pintype "passive"))
    )
    (net (code "43") (name "Net-(U1C-IN-)") (class "Default")
      (node (ref "R15") (pin "1") (pinfunction "1_1") (pintype "passive"))
      (node (ref "R24") (pin "2") (pinfunction "2_2") (pintype "passive"))
      (node (ref "U1") (pin "9") (pinfunction "IN-_9") (pintype "passive"))
    )
    (net (code "44") (name "Net-(U1C-OUT)") (class "Default")
      (node (ref "R15") (pin "2") (pinfunction "2_2") (pintype "passive"))
      (node (ref "R7") (pin "1") (pinfunction "1_1") (pintype "passive"))
      (node (ref "U1") (pin "8") (pinfunction "OUT_8") (pintype "passive"))
    )
    (net (code "45") (name "Net-(U1D-IN+)") (class "Default")
      (node (ref "R48") (pin "1") (pinfunction "1_1") (pintype "passive"))
      (node (ref "R49") (pin "2") (pinfunction "2_2") (pintype "passive"))
      (node (ref "U1") (pin "12") (pinfunction "IN+_12") (pintype "passive"))
    )
    (net (code "46") (name "Net-(U1D-IN-)") (class "Default")
      (node (ref "C34") (pin "1") (pinfunction "1_1") (pintype "passive"))
      (node (ref "R32") (pin "1") (pinfunction "1_1") (pintype "passive"))
      (node (ref "R33") (pin "2") (pinfunction "2_2") (pintype "passive"))
      (node (ref "U1") (pin "13") (pinfunction "IN-_13") (pintype "passive"))
    )
    (net (code "47") (name "Net-(U2A-IN+)") (class "Default")
      (node (ref "R17") (pin "1") (pinfunction "1_1") (pintype "passive"))
      (node (ref "U2") (pin "3") (pinfunction "IN+_3") (pintype "passive"))
    )
    (net (code "48") (name "Net-(U2A-IN-)") (class "Default")
      (node (ref "R14") (pin "2") (pinfunction "2_2") (pintype "passive"))
      (node (ref "U2") (pin "2") (pinfunction "IN-_2") (pintype "passive"))
    )
    (net (code "49") (name "Net-(U2A-OUT)") (class "Default")
      (node (ref "R14") (pin "1") (pinfunction "1_1") (pintype "passive"))
      (node (ref "R5") (pin "1") (pinfunction "1_1") (pintype "passive"))
      (node (ref "TP1") (pin "1") (pinfunction "1_1") (pintype "passive"))
      (node (ref "U2") (pin "1") (pinfunction "OUT_1") (pintype "passive"))
    )
    (net (code "50") (name "Net-(U2B-IN+)") (class "Default")
      (node (ref "R4") (pin "2") (pinfunction "2_2") (pintype "passive"))
      (node (ref "R5") (pin "2") (pinfunction "2_2") (pintype "passive"))
      (node (ref "U2") (pin "5") (pinfunction "IN+_5") (pintype "passive"))
    )
    (net (code "51") (name "Net-(U2B-IN-)") (class "Default")
      (node (ref "R3") (pin "1") (pinfunction "1_1") (pintype "passive"))
      (node (ref "R6") (pin "1") (pinfunction "1_1") (pintype "passive"))
      (node (ref "U2") (pin "6") (pinfunction "IN-_6") (pintype "passive"))
    )
    (net (code "52") (name "Net-(U2B-OUT)") (class "Default")
      (node (ref "R24") (pin "1") (pinfunction "1_1") (pintype "passive"))
      (node (ref "R6") (pin "2") (pinfunction "2_2") (pintype "passive"))
      (node (ref "U2") (pin "7") (pinfunction "OUT_7") (pintype "passive"))
    )
    (net (code "53") (name "Net-(U3A-IN+)") (class "Default")
      (node (ref "R25") (pin "1") (pinfunction "1_1") (pintype "passive"))
      (node (ref "R26") (pin "2") (pinfunction "2_2") (pintype "passive"))
      (node (ref "U3") (pin "3") (pinfunction "IN+_3") (pintype "passive"))
    )
    (net (code "54") (name "Net-(U3A-IN-)") (class "Default")
      (node (ref "R29") (pin "2") (pinfunction "2_2") (pintype "passive"))
      (node (ref "U3") (pin "2") (pinfunction "IN-_2") (pintype "passive"))
    )
    (net (code "55") (name "Net-(U3A-OUT)") (class "Default")
      (node (ref "R26") (pin "1") (pinfunction "1_1") (pintype "passive"))
      (node (ref "R30") (pin "1") (pinfunction "1_1") (pintype "passive"))
      (node (ref "TP4") (pin "1") (pinfunction "1_1") (pintype "passive"))
      (node (ref "U3") (pin "1") (pinfunction "OUT_1") (pintype "passive"))
    )
    (net (code "56") (name "Net-(U3B-IN+)") (class "Default")
      (node (ref "R18") (pin "1") (pinfunction "1_1") (pintype "passive"))
      (node (ref "R19") (pin "1") (pinfunction "1_1") (pintype "passive"))
      (node (ref "R31") (pin "2") (pinfunction "2_2") (pintype "passive"))
      (node (ref "U3") (pin "5") (pinfunction "IN+_5") (pintype "passive"))
    )
    (net (code "57") (name "Net-(U3B-IN-)") (class "Default")
      (node (ref "R21") (pin "1") (pinfunction "1_1") (pintype "passive"))
      (node (ref "R23") (pin "2") (pinfunction "2_2") (pintype "passive"))
      (node (ref "U3") (pin "6") (pinfunction "IN-_6") (pintype "passive"))
    )
    (net (code "58") (name "Net-(U3B-OUT)") (class "Default")
      (node (ref "R21") (pin "2") (pinfunction "2_2") (pintype "passive"))
      (node (ref "R29") (pin "1") (pinfunction "1_1") (pintype "passive"))
      (node (ref "U3") (pin "7") (pinfunction "OUT_7") (pintype "passive"))
    )
    (net (code "59") (name "Net-(U3C-IN+)") (class "Default")
      (node (ref "R46") (pin "1") (pinfunction "1_1") (pintype "passive"))
      (node (ref "R47") (pin "2") (pinfunction "2_2") (pintype "passive"))
      (node (ref "U3") (pin "10") (pinfunction "IN+_10") (pintype "passive"))
    )
    (net (code "60") (name "Net-(U3C-IN-)") (class "Default")
      (node (ref "C6") (pin "2") (pinfunction "2_2") (pintype "passive"))
      (node (ref "R16") (pin "1") (pinfunction "1_1") (pintype "passive"))
      (node (ref "R30") (pin "2") (pinfunction "2_2") (pintype "passive"))
      (node (ref "U3") (pin "9") (pinfunction "IN-_9") (pintype "passive"))
    )
    (net (code "61") (name "Net-(U3C-OUT)") (class "Default")
      (node (ref "P4") (pin "2") (pinfunction "2_2") (pintype "passive"))
      (node (ref "R16") (pin "2") (pinfunction "2_2") (pintype "passive"))
      (node (ref "R47") (pin "1") (pinfunction "1_1") (pintype "passive"))
      (node (ref "TP3") (pin "1") (pinfunction "1_1") (pintype "passive"))
      (node (ref "U3") (pin "8") (pinfunction "OUT_8") (pintype "passive"))
    )
    (net (code "62") (name "Net-(U4A-IN+)") (class "Default")
      (node (ref "R62") (pin "2") (pinfunction "2_2") (pintype "passive"))
      (node (ref "U4") (pin "3") (pinfunction "IN+_3") (pintype "passive"))
    )
    (net (code "63") (name "Net-(U4A-IN-)") (class "Default")
      (node (ref "R50") (pin "1") (pinfunction "1_1") (pintype "passive"))
      (node (ref "R60") (pin "2") (pinfunction "2_2") (pintype "passive"))
      (node (ref "U4") (pin "2") (pinfunction "IN-_2") (pintype "passive"))
    )
    (net (code "64") (name "Net-(U4A-OUT)") (class "Default")
      (node (ref "R50") (pin "2") (pinfunction "2_2") (pintype "passive"))
      (node (ref "U4") (pin "1") (pinfunction "OUT_1") (pintype "passive"))
      (node (ref "U4") (pin "5") (pinfunction "IN+_5") (pintype "passive"))
    )
    (net (code "65") (name "Net-(U4B-IN-)") (class "Default")
      (node (ref "C36") (pin "1") (pinfunction "1_1") (pintype "passive"))
      (node (ref "R51") (pin "1") (pinfunction "1_1") (pintype "passive"))
      (node (ref "R57") (pin "2") (pinfunction "2_2") (pintype "passive"))
      (node (ref "U4") (pin "6") (pinfunction "IN-_6") (pintype "passive"))
    )
    (net (code "66") (name "Net-(U4B-OUT)") (class "Default")
      (node (ref "C36") (pin "2") (pinfunction "2_2") (pintype "passive"))
      (node (ref "R51") (pin "2") (pinfunction "2_2") (pintype "passive"))
      (node (ref "R61") (pin "1") (pinfunction "1_1") (pintype "passive"))
      (node (ref "U4") (pin "7") (pinfunction "OUT_7") (pintype "passive"))
    )
    (net (code "67") (name "Net-(U4C-IN-)") (class "Default")
      (node (ref "R52") (pin "1") (pinfunction "1_1") (pintype "passive"))
      (node (ref "R54") (pin "1") (pinfunction "1_1") (pintype "passive"))
      (node (ref "R61") (pin "2") (pinfunction "2_2") (pintype "passive"))
      (node (ref "U4") (pin "9") (pinfunction "IN-_9") (pintype "passive"))
    )
    (net (code "68") (name "Net-(U4D-IN+)") (class "Default")
      (node (ref "C31") (pin "2") (pinfunction "2_2") (pintype "passive"))
      (node (ref "R55") (pin "1") (pinfunction "1_1") (pintype "passive"))
      (node (ref "R63") (pin "1") (pinfunction "1_1") (pintype "passive"))
      (node (ref "U4") (pin "12") (pinfunction "IN+_12") (pintype "passive"))
    )
    (net (code "69") (name "Net-(U4D-IN-)") (class "Default")
      (node (ref "C26") (pin "2") (pinfunction "2_2") (pintype "passive"))
      (node (ref "R53") (pin "1") (pinfunction "1_1") (pintype "passive"))
      (node (ref "R56") (pin "2") (pinfunction "2_2") (pintype "passive"))
      (node (ref "U4") (pin "13") (pinfunction "IN-_13") (pintype "passive"))
    )
    (net (code "70") (name "Net-(U4D-OUT)") (class "Default")
      (node (ref "C26") (pin "1") (pinfunction "1_1") (pintype "passive"))
      (node (ref "P2") (pin "1") (pinfunction "1_1") (pintype "passive"))
      (node (ref "R56") (pin "1") (pinfunction "1_1") (pintype "passive"))
      (node (ref "U4") (pin "14") (pinfunction "OUT_14") (pintype "passive"))
    )
    (net (code "71") (name "Net-(U5-AHI)") (class "Default")
      (node (ref "P4") (pin "1") (pinfunction "1_1") (pintype "passive"))
      (node (ref "U5") (pin "5") (pinfunction "BLI_5") (pintype "input"))
      (node (ref "U5") (pin "7") (pinfunction "AHI_7") (pintype "input"))
      (node (ref "U8") (pin "2") (pinfunction "A_2") (pintype "passive"))
    )
    (net (code "72") (name "Net-(U5-ALI)") (class "Default")
      (node (ref "U5") (pin "2") (pinfunction "BHI_2") (pintype "input"))
      (node (ref "U5") (pin "6") (pinfunction "ALI_6") (pintype "input"))
      (node (ref "U8") (pin "4") (pinfunction "Y_4") (pintype "passive"))
    )
    (net (code "73") (name "Net-(U5-HDEL)") (class "Default")
      (node (ref "R35") (pin "2") (pinfunction "2_2") (pintype "passive"))
      (node (ref "U5") (pin "8") (pinfunction "HDEL_8") (pintype "passive"))
    )
    (net (code "74") (name "Net-(U5-LDEL)") (class "Default")
      (node (ref "R36") (pin "2") (pinfunction "2_2") (pintype "passive"))
      (node (ref "U5") (pin "9") (pinfunction "LDEL_9") (pintype "passive"))
    )
    (net (code "75") (name "Net-(VR3-EN)") (class "Default")
      (node (ref "R44") (pin "1") (pinfunction "1_1") (pintype "passive"))
      (node (ref "VR3") (pin "3") (pinfunction "EN_3") (pintype "input"))
    )
    (net (code "76") (name "Net-(VR3-FIL)") (class "Default")
      (node (ref "C24") (pin "2") (pinfunction "2_2") (pintype "passive"))
      (node (ref "VR3") (pin "1") (pinfunction "FIL_1") (pintype "passive"))
    )
    (net (code "77") (name "unconnected-(U3D-IN+-Pad12)") (class "Default")
      (node (ref "U3") (pin "12") (pinfunction "IN+_12") (pintype "passive"))
    )
    (net (code "78") (name "unconnected-(U3D-IN--Pad13)") (class "Default")
      (node (ref "U3") (pin "13") (pinfunction "IN-_13") (pintype "passive"))
    )
    (net (code "79") (name "unconnected-(U3D-OUT-Pad14)") (class "Default")
      (node (ref "U3") (pin "14") (pinfunction "OUT_14") (pintype "passive"))
    )
  )
)
